# Sheet4.net
KiCad netlist of a schematic drawn in Altium Designer
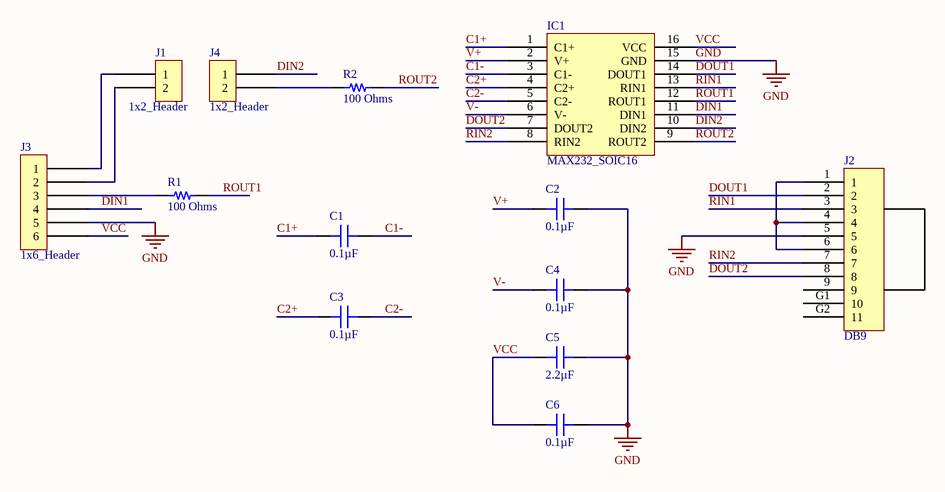
[diagram p0: Sheet4.SchDoc]

(export (version "E")
  (design (tool "Eeschema 10.0.6"))
  (components
    (comp (ref "C1")
      (value "0.1µF")
      (footprint "CAP 1206_3216 - 1.8MM")
      (description "CAP CER 0.1UF 100V C0G 1206")
      (fields
        (field (name "PART NUMBER") "C3216C0G2A104J160AC")
        (field (name "MANUFACTURER") "TDK Corporation")
      )
      (libsource (lib "Celestial Altium Library - altium_library") (part "Capacitor"))
    )
    (comp (ref "C2")
      (value "0.1µF")
      (footprint "CAP 1206_3216 - 1.8MM")
      (description "CAP CER 0.1UF 100V C0G 1206")
      (fields
        (field (name "PART NUMBER") "C3216C0G2A104J160AC")
        (field (name "MANUFACTURER") "TDK Corporation")
      )
      (libsource (lib "Celestial Altium Library - altium_library") (part "Capacitor"))
    )
    (comp (ref "C3")
      (value "0.1µF")
      (footprint "CAP 1206_3216 - 1.8MM")
      (description "CAP CER 0.1UF 100V C0G 1206")
      (fields
        (field (name "PART NUMBER") "C3216C0G2A104J160AC")
        (field (name "MANUFACTURER") "TDK Corporation")
      )
      (libsource (lib "Celestial Altium Library - altium_library") (part "Capacitor"))
    )
    (comp (ref "C4")
      (value "0.1µF")
      (footprint "CAP 1206_3216 - 1.8MM")
      (description "CAP CER 0.1UF 100V C0G 1206")
      (fields
        (field (name "PART NUMBER") "C3216C0G2A104J160AC")
        (field (name "MANUFACTURER") "TDK Corporation")
      )
      (libsource (lib "Celestial Altium Library - altium_library") (part "Capacitor"))
    )
    (comp (ref "C5")
      (value "2.2µF")
      (footprint "CAP 1206_3216 - 1.8MM")
      (description "CAP CER 2.2UF 25V X8R 1206")
      (fields
        (field (name "PART NUMBER") "CGA5L3X8R1E225M160AB")
        (field (name "MANUFACTURER") "TDK Corporation")
      )
      (libsource (lib "Celestial Altium Library - altium_library") (part "Capacitor"))
    )
    (comp (ref "C6")
      (value "0.1µF")
      (footprint "CAP 1206_3216 - 1.8MM")
      (description "CAP CER 0.1UF 100V C0G 1206")
      (fields
        (field (name "PART NUMBER") "C3216C0G2A104J160AC")
        (field (name "MANUFACTURER") "TDK Corporation")
      )
      (libsource (lib "Celestial Altium Library - altium_library") (part "Capacitor"))
    )
    (comp (ref "IC1")
      (value "MAX232_SOIC16")
      (footprint "SOIC127P1030X265-16N")
      (libsource (lib "Schlib1") (part "MAX232_SOIC16"))
    )
    (comp (ref "J1")
      (value "1x2_Header")
      (footprint "1x2_Header")
      (libsource (lib "Schlib1") (part "1x2_Header"))
    )
    (comp (ref "J2") (value "DB9") (footprint "DB9") (libsource (lib "Schlib1") (part "DB9")))
    (comp (ref "J3")
      (value "1x6_Header")
      (footprint "1x6_Header")
      (libsource (lib "Schlib1") (part "1x6_Header"))
    )
    (comp (ref "J4") (value "1x2_Header") (footprint "1x2_Header") (libsource (lib "") (part "1x2_Header_1")))
    (comp (ref "R1")
      (value "100 Ohms")
      (footprint "RES 2512_6432")
      (description "RES SMD 100 OHM 1% 1W 2512")
      (fields (field (name "PART NUMBER") "RC2512FK-07100RL") (field (name "MANUFACTURER") "Yageo"))
      (libsource (lib "Celestial Altium Library - altium_library") (part "Resistor"))
    )
    (comp (ref "R2")
      (value "100 Ohms")
      (footprint "RES 2512_6432")
      (description "RES SMD 100 OHM 1% 1W 2512")
      (fields (field (name "PART NUMBER") "RC2512FK-07100RL") (field (name "MANUFACTURER") "Yageo"))
      (libsource (lib "Celestial Altium Library - altium_library") (part "Resistor"))
    )
  )
  (nets
    (net (code "1") (name "/C1+") (class "Default")
      (node (ref "C1") (pin "1") (pinfunction "1_1") (pintype "passive"))
      (node (ref "IC1") (pin "1") (pinfunction "C1+_1") (pintype "passive"))
    )
    (net (code "2") (name "/C1-") (class "Default")
      (node (ref "C1") (pin "2") (pinfunction "2_2") (pintype "passive"))
      (node (ref "IC1") (pin "3") (pinfunction "C1-_3") (pintype "passive"))
    )
    (net (code "3") (name "/C2+") (class "Default")
      (node (ref "C3") (pin "2") (pinfunction "2_2") (pintype "passive"))
      (node (ref "IC1") (pin "4") (pinfunction "C2+_4") (pintype "passive"))
    )
    (net (code "4") (name "/C2-") (class "Default")
      (node (ref "C3") (pin "1") (pinfunction "1_1") (pintype "passive"))
      (node (ref "IC1") (pin "5") (pinfunction "C2-_5") (pintype "passive"))
    )
    (net (code "5") (name "/DIN1") (class "Default")
      (node (ref "IC1") (pin "11") (pinfunction "DIN1_11") (pintype "passive"))
      (node (ref "J3") (pin "4") (pinfunction "4_4") (pintype "passive"))
    )
    (net (code "6") (name "/DIN2") (class "Default")
      (node (ref "IC1") (pin "10") (pinfunction "DIN2_10") (pintype "passive"))
      (node (ref "J4") (pin "1") (pinfunction "1_1") (pintype "passive"))
    )
    (net (code "7") (name "/DOUT1") (class "Default")
      (node (ref "IC1") (pin "14") (pinfunction "DOUT1_14") (pintype "passive"))
      (node (ref "J2") (pin "2") (pinfunction "2_2") (pintype "passive"))
    )
    (net (code "8") (name "/DOUT2") (class "Default")
      (node (ref "IC1") (pin "7") (pinfunction "DOUT2_7") (pintype "passive"))
      (node (ref "J2") (pin "8") (pinfunction "8_8") (pintype "passive"))
    )
    (net (code "9") (name "/RIN1") (class "Default")
      (node (ref "IC1") (pin "13") (pinfunction "RIN1_13") (pintype "passive"))
      (node (ref "J2") (pin "3") (pinfunction "3_3") (pintype "passive"))
    )
    (net (code "10") (name "/RIN2") (class "Default")
      (node (ref "IC1") (pin "8") (pinfunction "RIN2_8") (pintype "passive"))
      (node (ref "J2") (pin "7") (pinfunction "7_7") (pintype "passive"))
    )
    (net (code "11") (name "/ROUT1") (class "Default")
      (node (ref "IC1") (pin "12") (pinfunction "ROUT1_12") (pintype "passive"))
      (node (ref "R1") (pin "2") (pinfunction "2_2") (pintype "passive"))
    )
    (net (code "12") (name "/ROUT2") (class "Default")
      (node (ref "IC1") (pin "9") (pinfunction "ROUT2_9") (pintype "passive"))
      (node (ref "R2") (pin "2") (pinfunction "2_2") (pintype "passive"))
    )
    (net (code "13") (name "/V+") (class "Default")
      (node (ref "C2") (pin "2") (pinfunction "2_2") (pintype "passive"))
      (node (ref "IC1") (pin "2") (pinfunction "V+_2") (pintype "passive"))
    )
    (net (code "14") (name "/V-") (class "Default")
      (node (ref "C4") (pin "1") (pinfunction "1_1") (pintype "passive"))
      (node (ref "IC1") (pin "6") (pinfunction "V-_6") (pintype "passive"))
    )
    (net (code "15") (name "/VCC") (class "Default")
      (node (ref "C5") (pin "1") (pinfunction "1_1") (pintype "passive"))
      (node (ref "C6") (pin "1") (pinfunction "1_1") (pintype "passive"))
      (node (ref "IC1") (pin "16") (pinfunction "VCC_16") (pintype "passive"))
      (node (ref "J3") (pin "6") (pinfunction "6_6") (pintype "passive"))
    )
    (net (code "16") (name "GND") (class "Default")
      (node (ref "C2") (pin "1") (pinfunction "1_1") (pintype "passive"))
      (node (ref "C4") (pin "2") (pinfunction "2_2") (pintype "passive"))
      (node (ref "C5") (pin "2") (pinfunction "2_2") (pintype "passive"))
      (node (ref "C6") (pin "2") (pinfunction "2_2") (pintype "passive"))
      (node (ref "IC1") (pin "15") (pinfunction "GND_15") (pintype "passive"))
      (node (ref "J2") (pin "5") (pinfunction "5_5") (pintype "passive"))
      (node (ref "J3") (pin "5") (pinfunction "5_5") (pintype "passive"))
    )
    (net (code "17") (name "Net-(J1-Pad1)") (class "Default")
      (node (ref "J1") (pin "1") (pinfunction "1_1") (pintype "passive"))
      (node (ref "J3") (pin "1") (pinfunction "1_1") (pintype "passive"))
    )
    (net (code "18") (name "Net-(J1-Pad2)") (class "Default")
      (node (ref "J1") (pin "2") (pinfunction "2_2") (pintype "passive"))
      (node (ref "J3") (pin "2") (pinfunction "2_2") (pintype "passive"))
    )
    (net (code "19") (name "Net-(J2-Pad1)") (class "Default")
      (node (ref "J2") (pin "1") (pinfunction "1_1") (pintype "passive"))
      (node (ref "J2") (pin "4") (pinfunction "4_4") (pintype "passive"))
      (node (ref "J2") (pin "6") (pinfunction "6_6") (pintype "passive"))
    )
    (net (code "20") (name "Net-(J3-Pad3)") (class "Default")
      (node (ref "J3") (pin "3") (pinfunction "3_3") (pintype "passive"))
      (node (ref "R1") (pin "1") (pinfunction "1_1") (pintype "passive"))
    )
    (net (code "21") (name "Net-(J4-Pad2)") (class "Default")
      (node (ref "J4") (pin "2") (pinfunction "2_2") (pintype "passive"))
      (node (ref "R2") (pin "1") (pinfunction "1_1") (pintype "passive"))
    )
    (net (code "22") (name "unconnected-(J2-10-PadG1)") (class "Default")
      (node (ref "J2") (pin "G1") (pinfunction "10_G1") (pintype "passive"))
    )
    (net (code "23") (name "unconnected-(J2-11-PadG2)") (class "Default")
      (node (ref "J2") (pin "G2") (pinfunction "11_G2") (pintype "passive"))
    )
    (net (code "24") (name "unconnected-(J2-Pad9)") (class "Default")
      (node (ref "J2") (pin "9") (pinfunction "9_9") (pintype "passive"))
    )
  )
)
